# PI_R3_REV1_BLOCK_CAP.net
KiCad netlist of a schematic drawn in Altium Designer
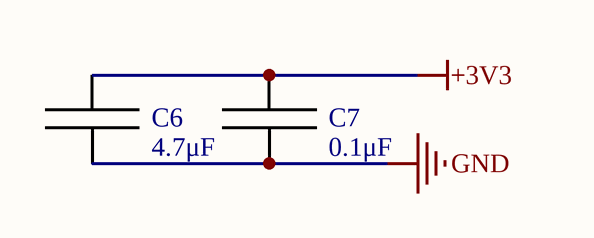
[diagram p0: PI_R3_REV1_BLOCK_CAP.SchDoc]

(export (version "E")
  (design (tool "Eeschema 10.0.6"))
  (components
    (comp (ref "C6")
      (value "4.7μF")
      (footprint "CAP: 0402")
      (fields (field (name "VOLTAGE") "??V") (field (name "Comment") "Cap_0402"))
      (libsource (lib "capacitor") (part "Cap_0402"))
    )
    (comp (ref "C7")
      (value "0.1μF")
      (footprint "CAP: 0402")
      (fields (field (name "VOLTAGE") "??V") (field (name "Comment") "Cap_0402"))
      (libsource (lib "capacitor") (part "Cap_0402"))
    )
  )
  (nets
    (net (code "1") (name "+3V3") (class "Default")
      (node (ref "C6") (pin "2") (pinfunction "2_2") (pintype "passive"))
      (node (ref "C7") (pin "2") (pinfunction "2_2") (pintype "passive"))
    )
    (net (code "2") (name "GND") (class "Default")
      (node (ref "C6") (pin "1") (pinfunction "1_1") (pintype "passive"))
      (node (ref "C7") (pin "1") (pinfunction "1_1") (pintype "passive"))
    )
  )
)
